# connector_board.net
KiCad netlist of a schematic drawn in EAGLE
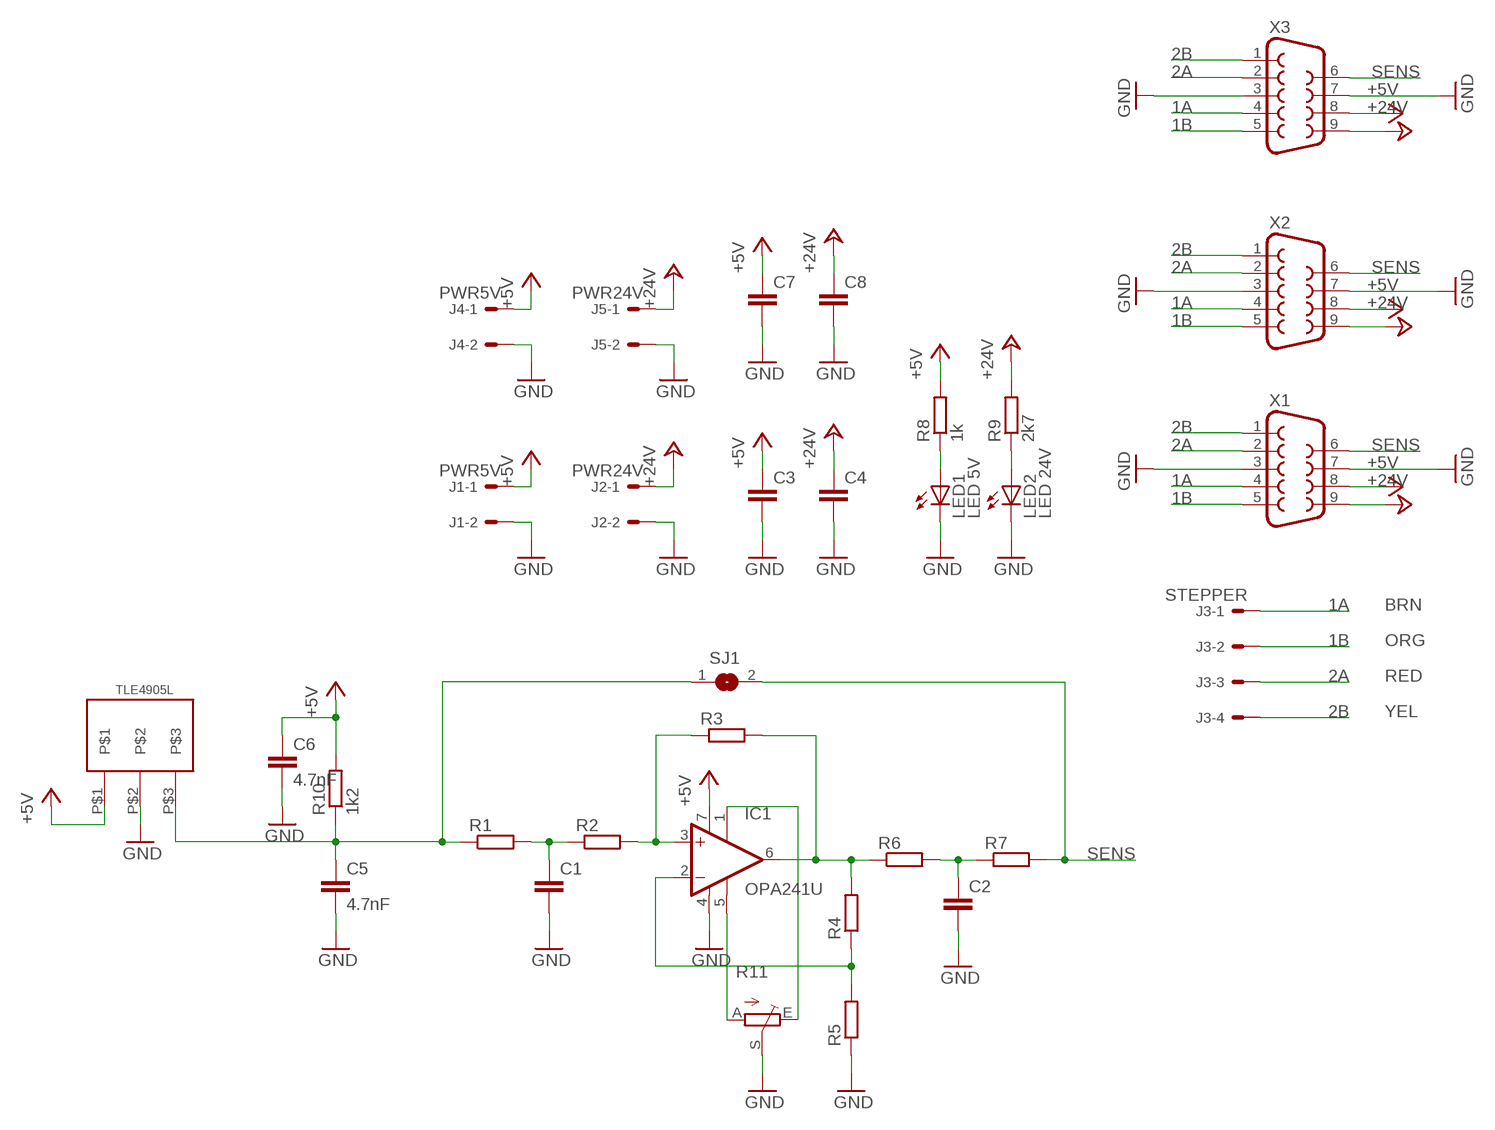
[diagram p0: schematic, sheet 1]

(export (version "E")
  (design (tool "Eeschema 10.0.6"))
  (components
    (comp (ref "C1")
      (value "C-EUC0805K")
      (footprint "eagle-import:C0805K")
      (libsource (lib "eagle-import") (part "C-EUC0805K"))
    )
    (comp (ref "C2")
      (value "C-EUC0805K")
      (footprint "eagle-import:C0805K")
      (libsource (lib "eagle-import") (part "C-EUC0805K"))
    )
    (comp (ref "C3")
      (value "C-EUC0805K")
      (footprint "eagle-import:C0805K")
      (libsource (lib "eagle-import") (part "C-EUC0805K"))
    )
    (comp (ref "C4")
      (value "C-EUC0805K")
      (footprint "eagle-import:C0805K")
      (libsource (lib "eagle-import") (part "C-EUC0805K"))
    )
    (comp (ref "C5")
      (value "4.7nF")
      (footprint "eagle-import:C0805K")
      (libsource (lib "eagle-import") (part "C-EUC0805K"))
    )
    (comp (ref "C6")
      (value "4.7nF")
      (footprint "eagle-import:C0805K")
      (libsource (lib "eagle-import") (part "C-EUC0805K"))
    )
    (comp (ref "C7")
      (value "C-EUC0805K")
      (footprint "eagle-import:C0805K")
      (libsource (lib "eagle-import") (part "C-EUC0805K"))
    )
    (comp (ref "C8")
      (value "C-EUC0805K")
      (footprint "eagle-import:C0805K")
      (libsource (lib "eagle-import") (part "C-EUC0805K"))
    )
    (comp (ref "IC1")
      (value "OPA241U")
      (footprint "eagle-import:SO08")
      (libsource (lib "eagle-import") (part "OPA241U"))
    )
    (comp (ref "J1")
      (value "PWR5V")
      (footprint "eagle-import:7395-02")
      (libsource (lib "eagle-import") (part "22-?-0205-7028"))
    )
    (comp (ref "J2")
      (value "PWR24V")
      (footprint "eagle-import:7395-02")
      (libsource (lib "eagle-import") (part "22-?-0205-7028"))
    )
    (comp (ref "J3")
      (value "STEPPER")
      (footprint "eagle-import:7395-04")
      (libsource (lib "eagle-import") (part "22-?-0405-7048"))
    )
    (comp (ref "J4")
      (value "PWR5V")
      (footprint "eagle-import:7395-02")
      (libsource (lib "eagle-import") (part "22-?-0205-7028"))
    )
    (comp (ref "J5")
      (value "PWR24V")
      (footprint "eagle-import:7395-02")
      (libsource (lib "eagle-import") (part "22-?-0205-7028"))
    )
    (comp (ref "LED1")
      (value "LED 5V")
      (footprint "eagle-import:CHIPLED_0805")
      (libsource (lib "eagle-import") (part "LEDCHIPLED_0805"))
    )
    (comp (ref "LED2")
      (value "LED 24V")
      (footprint "eagle-import:CHIPLED_0805")
      (libsource (lib "eagle-import") (part "LEDCHIPLED_0805"))
    )
    (comp (ref "R1")
      (value "R-EU_M0805")
      (footprint "eagle-import:M0805")
      (libsource (lib "eagle-import") (part "R-EU_M0805"))
    )
    (comp (ref "R2")
      (value "R-EU_M0805")
      (footprint "eagle-import:M0805")
      (libsource (lib "eagle-import") (part "R-EU_M0805"))
    )
    (comp (ref "R3")
      (value "R-EU_M0805")
      (footprint "eagle-import:M0805")
      (libsource (lib "eagle-import") (part "R-EU_M0805"))
    )
    (comp (ref "R4")
      (value "R-EU_M0805")
      (footprint "eagle-import:M0805")
      (libsource (lib "eagle-import") (part "R-EU_M0805"))
    )
    (comp (ref "R5")
      (value "R-EU_M0805")
      (footprint "eagle-import:M0805")
      (libsource (lib "eagle-import") (part "R-EU_M0805"))
    )
    (comp (ref "R6")
      (value "R-EU_M0805")
      (footprint "eagle-import:M0805")
      (libsource (lib "eagle-import") (part "R-EU_M0805"))
    )
    (comp (ref "R7")
      (value "R-EU_M0805")
      (footprint "eagle-import:M0805")
      (libsource (lib "eagle-import") (part "R-EU_M0805"))
    )
    (comp (ref "R8")
      (value "1k")
      (footprint "eagle-import:M0805")
      (libsource (lib "eagle-import") (part "R-EU_M0805"))
    )
    (comp (ref "R9")
      (value "2k7")
      (footprint "eagle-import:M0805")
      (libsource (lib "eagle-import") (part "R-EU_M0805"))
    )
    (comp (ref "R10")
      (value "1k2")
      (footprint "eagle-import:M0805")
      (libsource (lib "eagle-import") (part "R-EU_M0805"))
    )
    (comp (ref "R11")
      (value "TRIM_EU-B64Y")
      (footprint "eagle-import:B64Y")
      (libsource (lib "eagle-import") (part "TRIM_EU-B64Y"))
    )
    (comp (ref "SJ1") (value "SJ") (footprint "eagle-import:SJ") (libsource (lib "eagle-import") (part "SJ")))
    (comp (ref "U$1")
      (value "TLE4905L")
      (footprint "eagle-import:TLE4905L")
      (libsource (lib "eagle-import") (part "TLE4905L"))
    )
    (comp (ref "X1")
      (value "F09HP")
      (footprint "eagle-import:F09HP")
      (libsource (lib "eagle-import") (part "F09HP"))
    )
    (comp (ref "X2")
      (value "F09HP")
      (footprint "eagle-import:F09HP")
      (libsource (lib "eagle-import") (part "F09HP"))
    )
    (comp (ref "X3")
      (value "F09HP")
      (footprint "eagle-import:F09HP")
      (libsource (lib "eagle-import") (part "F09HP"))
    )
  )
  (nets
    (net (code "1") (name "+5V") (class "Default")
      (node (ref "C3") (pin "1") (pinfunction "1_1") (pintype "passive"))
      (node (ref "C6") (pin "1") (pinfunction "1_1") (pintype "passive"))
      (node (ref "C7") (pin "1") (pinfunction "1_1") (pintype "passive"))
      (node (ref "IC1") (pin "7") (pinfunction "V+_7") (pintype "power_in"))
      (node (ref "J1") (pin "1") (pinfunction "S_1") (pintype "passive"))
      (node (ref "J4") (pin "1") (pinfunction "S_1") (pintype "passive"))
      (node (ref "R10") (pin "2") (pinfunction "2_2") (pintype "passive"))
      (node (ref "R8") (pin "2") (pinfunction "2_2") (pintype "passive"))
      (node (ref "U$1") (pin "P$1") (pinfunction "P$1_P$1") (pintype "bidirectional"))
      (node (ref "X1") (pin "8") (pinfunction "8_8") (pintype "passive"))
      (node (ref "X2") (pin "8") (pinfunction "8_8") (pintype "passive"))
      (node (ref "X3") (pin "8") (pinfunction "8_8") (pintype "passive"))
    )
    (net (code "2") (name "+24V") (class "Default")
      (node (ref "C4") (pin "1") (pinfunction "1_1") (pintype "passive"))
      (node (ref "C8") (pin "1") (pinfunction "1_1") (pintype "passive"))
      (node (ref "J2") (pin "1") (pinfunction "S_1") (pintype "passive"))
      (node (ref "J5") (pin "1") (pinfunction "S_1") (pintype "passive"))
      (node (ref "R9") (pin "2") (pinfunction "2_2") (pintype "passive"))
      (node (ref "X1") (pin "9") (pinfunction "9_9") (pintype "passive"))
      (node (ref "X2") (pin "9") (pinfunction "9_9") (pintype "passive"))
      (node (ref "X3") (pin "9") (pinfunction "9_9") (pintype "passive"))
    )
    (net (code "3") (name "/1A") (class "Default")
      (node (ref "J3") (pin "1") (pinfunction "S_1") (pintype "passive"))
      (node (ref "X1") (pin "4") (pinfunction "4_4") (pintype "passive"))
      (node (ref "X2") (pin "4") (pinfunction "4_4") (pintype "passive"))
      (node (ref "X3") (pin "4") (pinfunction "4_4") (pintype "passive"))
    )
    (net (code "4") (name "/1B") (class "Default")
      (node (ref "J3") (pin "2") (pinfunction "S_2") (pintype "passive"))
      (node (ref "X1") (pin "5") (pinfunction "5_5") (pintype "passive"))
      (node (ref "X2") (pin "5") (pinfunction "5_5") (pintype "passive"))
      (node (ref "X3") (pin "5") (pinfunction "5_5") (pintype "passive"))
    )
    (net (code "5") (name "/2A") (class "Default")
      (node (ref "J3") (pin "3") (pinfunction "S_3") (pintype "passive"))
      (node (ref "X1") (pin "2") (pinfunction "2_2") (pintype "passive"))
      (node (ref "X2") (pin "2") (pinfunction "2_2") (pintype "passive"))
      (node (ref "X3") (pin "2") (pinfunction "2_2") (pintype "passive"))
    )
    (net (code "6") (name "/2B") (class "Default")
      (node (ref "J3") (pin "4") (pinfunction "S_4") (pintype "passive"))
      (node (ref "X1") (pin "1") (pinfunction "1_1") (pintype "passive"))
      (node (ref "X2") (pin "1") (pinfunction "1_1") (pintype "passive"))
      (node (ref "X3") (pin "1") (pinfunction "1_1") (pintype "passive"))
    )
    (net (code "7") (name "/SENS") (class "Default")
      (node (ref "R7") (pin "2") (pinfunction "2_2") (pintype "passive"))
      (node (ref "SJ1") (pin "2") (pinfunction "2_2") (pintype "passive"))
      (node (ref "X1") (pin "6") (pinfunction "6_6") (pintype "passive"))
      (node (ref "X2") (pin "6") (pinfunction "6_6") (pintype "passive"))
      (node (ref "X3") (pin "6") (pinfunction "6_6") (pintype "passive"))
    )
    (net (code "8") (name "GND") (class "Default")
      (node (ref "C1") (pin "2") (pinfunction "2_2") (pintype "passive"))
      (node (ref "C2") (pin "2") (pinfunction "2_2") (pintype "passive"))
      (node (ref "C3") (pin "2") (pinfunction "2_2") (pintype "passive"))
      (node (ref "C4") (pin "2") (pinfunction "2_2") (pintype "passive"))
      (node (ref "C5") (pin "2") (pinfunction "2_2") (pintype "passive"))
      (node (ref "C6") (pin "2") (pinfunction "2_2") (pintype "passive"))
      (node (ref "C7") (pin "2") (pinfunction "2_2") (pintype "passive"))
      (node (ref "C8") (pin "2") (pinfunction "2_2") (pintype "passive"))
      (node (ref "IC1") (pin "4") (pinfunction "V-_4") (pintype "power_in"))
      (node (ref "J1") (pin "2") (pinfunction "S_2") (pintype "passive"))
      (node (ref "J2") (pin "2") (pinfunction "S_2") (pintype "passive"))
      (node (ref "J4") (pin "2") (pinfunction "S_2") (pintype "passive"))
      (node (ref "J5") (pin "2") (pinfunction "S_2") (pintype "passive"))
      (node (ref "LED1") (pin "C") (pinfunction "C_C") (pintype "passive"))
      (node (ref "LED2") (pin "C") (pinfunction "C_C") (pintype "passive"))
      (node (ref "R11") (pin "S") (pinfunction "S_S") (pintype "passive"))
      (node (ref "R5") (pin "1") (pinfunction "1_1") (pintype "passive"))
      (node (ref "U$1") (pin "P$2") (pinfunction "P$2_P$2") (pintype "bidirectional"))
      (node (ref "X1") (pin "3") (pinfunction "3_3") (pintype "passive"))
      (node (ref "X1") (pin "7") (pinfunction "7_7") (pintype "passive"))
      (node (ref "X2") (pin "3") (pinfunction "3_3") (pintype "passive"))
      (node (ref "X2") (pin "7") (pinfunction "7_7") (pintype "passive"))
      (node (ref "X3") (pin "3") (pinfunction "3_3") (pintype "passive"))
      (node (ref "X3") (pin "7") (pinfunction "7_7") (pintype "passive"))
    )
    (net (code "9") (name "Net-(C1-Pad1)") (class "Default")
      (node (ref "C1") (pin "1") (pinfunction "1_1") (pintype "passive"))
      (node (ref "R1") (pin "2") (pinfunction "2_2") (pintype "passive"))
      (node (ref "R2") (pin "1") (pinfunction "1_1") (pintype "passive"))
    )
    (net (code "10") (name "Net-(C2-Pad1)") (class "Default")
      (node (ref "C2") (pin "1") (pinfunction "1_1") (pintype "passive"))
      (node (ref "R6") (pin "2") (pinfunction "2_2") (pintype "passive"))
      (node (ref "R7") (pin "1") (pinfunction "1_1") (pintype "passive"))
    )
    (net (code "11") (name "Net-(C5-Pad1)") (class "Default")
      (node (ref "C5") (pin "1") (pinfunction "1_1") (pintype "passive"))
      (node (ref "R1") (pin "1") (pinfunction "1_1") (pintype "passive"))
      (node (ref "R10") (pin "1") (pinfunction "1_1") (pintype "passive"))
      (node (ref "SJ1") (pin "1") (pinfunction "1_1") (pintype "passive"))
      (node (ref "U$1") (pin "P$3") (pinfunction "P$3_P$3") (pintype "bidirectional"))
    )
    (net (code "12") (name "Net-(IC1-+IN)") (class "Default")
      (node (ref "IC1") (pin "3") (pinfunction "+IN_3") (pintype "input"))
      (node (ref "R2") (pin "2") (pinfunction "2_2") (pintype "passive"))
      (node (ref "R3") (pin "1") (pinfunction "1_1") (pintype "passive"))
    )
    (net (code "13") (name "Net-(IC1--IN)") (class "Default")
      (node (ref "IC1") (pin "2") (pinfunction "-IN_2") (pintype "input"))
      (node (ref "R4") (pin "1") (pinfunction "1_1") (pintype "passive"))
      (node (ref "R5") (pin "2") (pinfunction "2_2") (pintype "passive"))
    )
    (net (code "14") (name "Net-(IC1-OUT)") (class "Default")
      (node (ref "IC1") (pin "6") (pinfunction "OUT_6") (pintype "output"))
      (node (ref "R3") (pin "2") (pinfunction "2_2") (pintype "passive"))
      (node (ref "R4") (pin "2") (pinfunction "2_2") (pintype "passive"))
      (node (ref "R6") (pin "1") (pinfunction "1_1") (pintype "passive"))
    )
    (net (code "15") (name "Net-(IC1-TRIM1)") (class "Default")
      (node (ref "IC1") (pin "1") (pinfunction "TRIM1_1") (pintype "passive"))
      (node (ref "R11") (pin "E") (pinfunction "E_E") (pintype "passive"))
    )
    (net (code "16") (name "Net-(IC1-TRIM2)") (class "Default")
      (node (ref "IC1") (pin "5") (pinfunction "TRIM2_5") (pintype "passive"))
      (node (ref "R11") (pin "A") (pinfunction "A_A") (pintype "passive"))
    )
    (net (code "17") (name "Net-(LED1-PadA)") (class "Default")
      (node (ref "LED1") (pin "A") (pinfunction "A_A") (pintype "passive"))
      (node (ref "R8") (pin "1") (pinfunction "1_1") (pintype "passive"))
    )
    (net (code "18") (name "Net-(LED2-PadA)") (class "Default")
      (node (ref "LED2") (pin "A") (pinfunction "A_A") (pintype "passive"))
      (node (ref "R9") (pin "1") (pinfunction "1_1") (pintype "passive"))
    )
  )
)
